# AT_Guard_Simple_Mems.net
KiCad netlist of a schematic drawn in Altium Designer
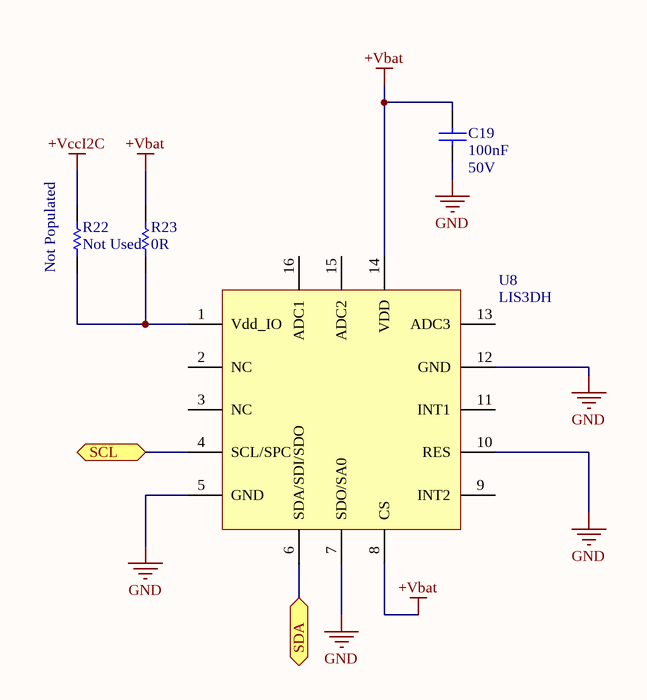
[diagram p0: AT Guard Simple Mems.SchDoc]

(export (version "E")
  (design (tool "Eeschema 10.0.6"))
  (components
    (comp (ref "C19")
      (value "100nF")
      (footprint "3-0603_L")
      (description "Capacitor")
      (fields
        (field (name "VOLTAGE") "50V")
        (field (name "Comment") "Cap")
        (field (name "PUBLISHER") "Altium Limited")
      )
      (libsource (lib "Erdem_05112012") (part "Cap"))
    )
    (comp (ref "R22")
      (value "Not Used")
      (footprint "3-0603_L")
      (description "Resistor")
      (fields (field (name "Comment") "Res1") (field (name "PUBLISHER") "Altium Limited"))
      (libsource (lib "Erdem_05112012") (part "Res1"))
    )
    (comp (ref "R23")
      (value "0R")
      (footprint "3-0603_L")
      (description "Resistor")
      (fields (field (name "Comment") "Res1") (field (name "PUBLISHER") "Altium Limited"))
      (libsource (lib "Erdem_05112012") (part "Res1"))
    )
    (comp (ref "U8")
      (value "LIS3DH")
      (footprint "LGA 16")
      (description "3-axis - ±2g analog output “nano” accelerometer")
      (fields (field (name "PUBLISHER") "Altium Limited"))
      (libsource (lib "Erdem_05112012") (part "LIS3DH"))
    )
  )
  (nets
    (net (code "1") (name "+Vbat") (class "Default")
      (node (ref "C19") (pin "1") (pinfunction "1_1") (pintype "passive"))
      (node (ref "R23") (pin "1") (pinfunction "1_1") (pintype "passive"))
      (node (ref "U8") (pin "14") (pinfunction "VDD_14") (pintype "passive"))
      (node (ref "U8") (pin "8") (pinfunction "CS_8") (pintype "passive"))
    )
    (net (code "2") (name "+VccI2C") (class "Default")
      (node (ref "R22") (pin "1") (pinfunction "1_1") (pintype "passive"))
    )
    (net (code "3") (name "/SCL") (class "Default")
      (node (ref "U8") (pin "4") (pinfunction "SCL/SPC_4") (pintype "passive"))
    )
    (net (code "4") (name "/SDA") (class "Default")
      (node (ref "U8") (pin "6") (pinfunction "SDA/SDI/SDO_6") (pintype "passive"))
    )
    (net (code "5") (name "GND") (class "Default")
      (node (ref "C19") (pin "2") (pinfunction "2_2") (pintype "passive"))
      (node (ref "U8") (pin "10") (pinfunction "RES_10") (pintype "passive"))
      (node (ref "U8") (pin "12") (pinfunction "GND_12") (pintype "passive"))
      (node (ref "U8") (pin "5") (pinfunction "GND_5") (pintype "passive"))
      (node (ref "U8") (pin "7") (pinfunction "SDO/SA0_7") (pintype "passive"))
    )
    (net (code "6") (name "Net-(U8-Vdd_IO)") (class "Default")
      (node (ref "R22") (pin "2") (pinfunction "2_2") (pintype "passive"))
      (node (ref "R23") (pin "2") (pinfunction "2_2") (pintype "passive"))
      (node (ref "U8") (pin "1") (pinfunction "Vdd_IO_1") (pintype "passive"))
    )
    (net (code "7") (name "unconnected-(U8-ADC1-Pad16)") (class "Default")
      (node (ref "U8") (pin "16") (pinfunction "ADC1_16") (pintype "passive"))
    )
    (net (code "8") (name "unconnected-(U8-ADC2-Pad15)") (class "Default")
      (node (ref "U8") (pin "15") (pinfunction "ADC2_15") (pintype "passive"))
    )
    (net (code "9") (name "unconnected-(U8-ADC3-Pad13)") (class "Default")
      (node (ref "U8") (pin "13") (pinfunction "ADC3_13") (pintype "passive"))
    )
    (net (code "10") (name "unconnected-(U8-INT1-Pad11)") (class "Default")
      (node (ref "U8") (pin "11") (pinfunction "INT1_11") (pintype "passive"))
    )
    (net (code "11") (name "unconnected-(U8-INT2-Pad9)") (class "Default")
      (node (ref "U8") (pin "9") (pinfunction "INT2_9") (pintype "passive"))
    )
    (net (code "12") (name "unconnected-(U8-NC-Pad2)") (class "Default")
      (node (ref "U8") (pin "2") (pinfunction "NC_2") (pintype "passive"))
    )
    (net (code "13") (name "unconnected-(U8-NC-Pad3)") (class "Default")
      (node (ref "U8") (pin "3") (pinfunction "NC_3") (pintype "passive"))
    )
  )
)
